# bqZUM_Autoreset.net
KiCad netlist of a schematic drawn in Altium Designer
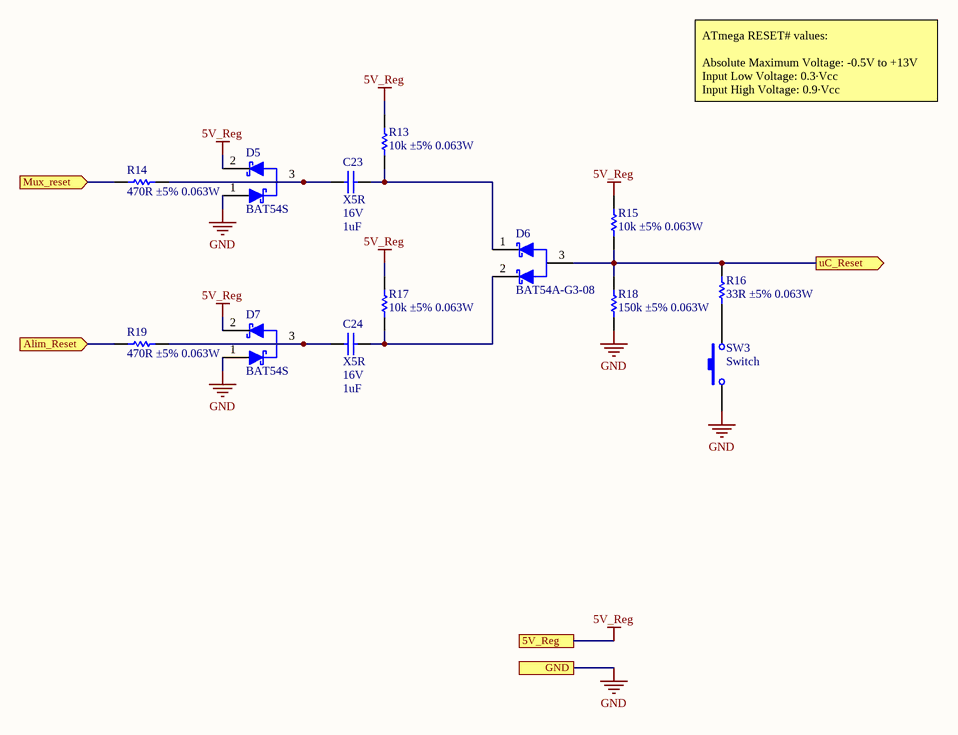
[diagram p0: bqZUM_Autoreset.SchDoc]

(export (version "E")
  (design (tool "Eeschema 10.0.6"))
  (components
    (comp (ref "C23")
      (value "Capacitor")
      (footprint "C0603")
      (fields
        (field (name "DIELECTRIC") "X5R")
        (field (name "VOLTAGE") "16V")
        (field (name "CAPACITANCE") "1uF")
        (field (name "TOLERANCE") "±10%")
        (field (name "MANUFACTURER") "Kemet")
      )
      (libsource (lib "Pasives_Capacitor_SMD") (part "Capacitor"))
    )
    (comp (ref "C24")
      (value "Capacitor")
      (footprint "C0603")
      (fields
        (field (name "DIELECTRIC") "X5R")
        (field (name "VOLTAGE") "16V")
        (field (name "CAPACITANCE") "1uF")
        (field (name "TOLERANCE") "±10%")
        (field (name "MANUFACTURER") "Kemet")
      )
      (libsource (lib "Pasives_Capacitor_SMD") (part "Capacitor"))
    )
    (comp (ref "D5")
      (value "BAT54S")
      (footprint "SOT23-3")
      (description "Dual Schottky Diode")
      (fields (field (name "MANUFACTURER") "NXP"))
      (libsource (lib "Semiconductors_Diodes") (part "Dual Schottky"))
    )
    (comp (ref "D6")
      (value "BAT54A-G3-08")
      (footprint "SOT23-3")
      (description "Dual Schottky Diode Common Anode")
      (fields (field (name "MANUFACTURER") "Vishay"))
      (libsource (lib "Semiconductors_Diodes") (part "Dual_Diode_Schottky_A"))
    )
    (comp (ref "D7")
      (value "BAT54S")
      (footprint "SOT23-3")
      (description "Dual Schottky Diode")
      (fields (field (name "MANUFACTURER") "NXP"))
      (libsource (lib "Semiconductors_Diodes") (part "Dual Schottky"))
    )
    (comp (ref "R13")
      (value "10k ±5% 0.063W")
      (footprint "R0402")
      (description "Resistor")
      (fields (field (name "TOLERANCE") "±5%") (field (name "POWER") "0.063W"))
      (libsource (lib "Pasives_Resistor_SMD") (part "Resistor"))
    )
    (comp (ref "R14")
      (value "470R ±5% 0.063W")
      (footprint "R0402")
      (description "Resistor")
      (fields (field (name "TOLERANCE") "±5%") (field (name "POWER") "0.063W"))
      (libsource (lib "Pasives_Resistor_SMD") (part "Resistor"))
    )
    (comp (ref "R15")
      (value "10k ±5% 0.063W")
      (footprint "R0402")
      (description "Resistor")
      (fields (field (name "TOLERANCE") "±5%") (field (name "POWER") "0.063W"))
      (libsource (lib "Pasives_Resistor_SMD") (part "Resistor"))
    )
    (comp (ref "R16")
      (value "33R ±5% 0.063W")
      (footprint "R0402")
      (description "Resistor")
      (fields (field (name "TOLERANCE") "±5%") (field (name "POWER") "0.063W"))
      (libsource (lib "Pasives_Resistor_SMD") (part "Resistor"))
    )
    (comp (ref "R17")
      (value "10k ±5% 0.063W")
      (footprint "R0402")
      (description "Resistor")
      (fields (field (name "TOLERANCE") "±5%") (field (name "POWER") "0.063W"))
      (libsource (lib "Pasives_Resistor_SMD") (part "Resistor"))
    )
    (comp (ref "R18")
      (value "150k ±5% 0.063W")
      (footprint "R0402")
      (description "Resistor")
      (fields (field (name "TOLERANCE") "±5%") (field (name "POWER") "0.063W"))
      (libsource (lib "Pasives_Resistor_SMD") (part "Resistor"))
    )
    (comp (ref "R19")
      (value "470R ±5% 0.063W")
      (footprint "R0402")
      (description "Resistor")
      (fields (field (name "TOLERANCE") "±5%") (field (name "POWER") "0.063W"))
      (libsource (lib "Pasives_Resistor_SMD") (part "Resistor"))
    )
    (comp (ref "SW3")
      (value "Switch")
      (footprint "SW_Vert_THT_7.5x6x6.5")
      (description "Micro miniature pushbutton surface Switch")
      (fields (field (name "MANUFACTURER") "C&K Components"))
      (libsource (lib "Electromechanical") (part "Switch"))
    )
  )
  (nets
    (net (code "1") (name "/Alim_Reset") (class "Default")
      (node (ref "R19") (pin "1") (pinfunction "1_1") (pintype "passive"))
    )
    (net (code "2") (name "/Mux_reset") (class "Default")
      (node (ref "R14") (pin "1") (pinfunction "1_1") (pintype "passive"))
    )
    (net (code "3") (name "/uC_Reset") (class "Default")
      (node (ref "D6") (pin "3") (pinfunction "K_3") (pintype "passive"))
      (node (ref "R15") (pin "1") (pinfunction "1_1") (pintype "passive"))
      (node (ref "R16") (pin "2") (pinfunction "2_2") (pintype "passive"))
      (node (ref "R18") (pin "2") (pinfunction "2_2") (pintype "passive"))
    )
    (net (code "4") (name "5V_Reg") (class "Default")
      (node (ref "D5") (pin "2") (pinfunction "K2_2") (pintype "passive"))
      (node (ref "D7") (pin "2") (pinfunction "K2_2") (pintype "passive"))
      (node (ref "R13") (pin "2") (pinfunction "2_2") (pintype "passive"))
      (node (ref "R15") (pin "2") (pinfunction "2_2") (pintype "passive"))
      (node (ref "R17") (pin "2") (pinfunction "2_2") (pintype "passive"))
    )
    (net (code "5") (name "GND") (class "Default")
      (node (ref "D5") (pin "1") (pinfunction "A_1") (pintype "passive"))
      (node (ref "D7") (pin "1") (pinfunction "A_1") (pintype "passive"))
      (node (ref "R18") (pin "1") (pinfunction "1_1") (pintype "passive"))
      (node (ref "SW3") (pin "2") (pinfunction "2_2") (pintype "passive"))
    )
    (net (code "6") (name "Net-(D5-K1)") (class "Default")
      (node (ref "C23") (pin "1") (pinfunction "1_1") (pintype "passive"))
      (node (ref "D5") (pin "3") (pinfunction "K1_3") (pintype "passive"))
      (node (ref "R14") (pin "2") (pinfunction "2_2") (pintype "passive"))
    )
    (net (code "7") (name "Net-(D6-A1)") (class "Default")
      (node (ref "C23") (pin "2") (pinfunction "2_2") (pintype "passive"))
      (node (ref "D6") (pin "1") (pinfunction "A1_1") (pintype "passive"))
      (node (ref "R13") (pin "1") (pinfunction "1_1") (pintype "passive"))
    )
    (net (code "8") (name "Net-(D6-A2)") (class "Default")
      (node (ref "C24") (pin "2") (pinfunction "2_2") (pintype "passive"))
      (node (ref "D6") (pin "2") (pinfunction "A2_2") (pintype "passive"))
      (node (ref "R17") (pin "1") (pinfunction "1_1") (pintype "passive"))
    )
    (net (code "9") (name "Net-(D7-K1)") (class "Default")
      (node (ref "C24") (pin "1") (pinfunction "1_1") (pintype "passive"))
      (node (ref "D7") (pin "3") (pinfunction "K1_3") (pintype "passive"))
      (node (ref "R19") (pin "2") (pinfunction "2_2") (pintype "passive"))
    )
    (net (code "10") (name "Net-(R16-Pad1)") (class "Default")
      (node (ref "R16") (pin "1") (pinfunction "1_1") (pintype "passive"))
      (node (ref "SW3") (pin "1") (pinfunction "1_1") (pintype "passive"))
    )
  )
)
